# Supplements.net
KiCad netlist of a schematic drawn in Altium Designer
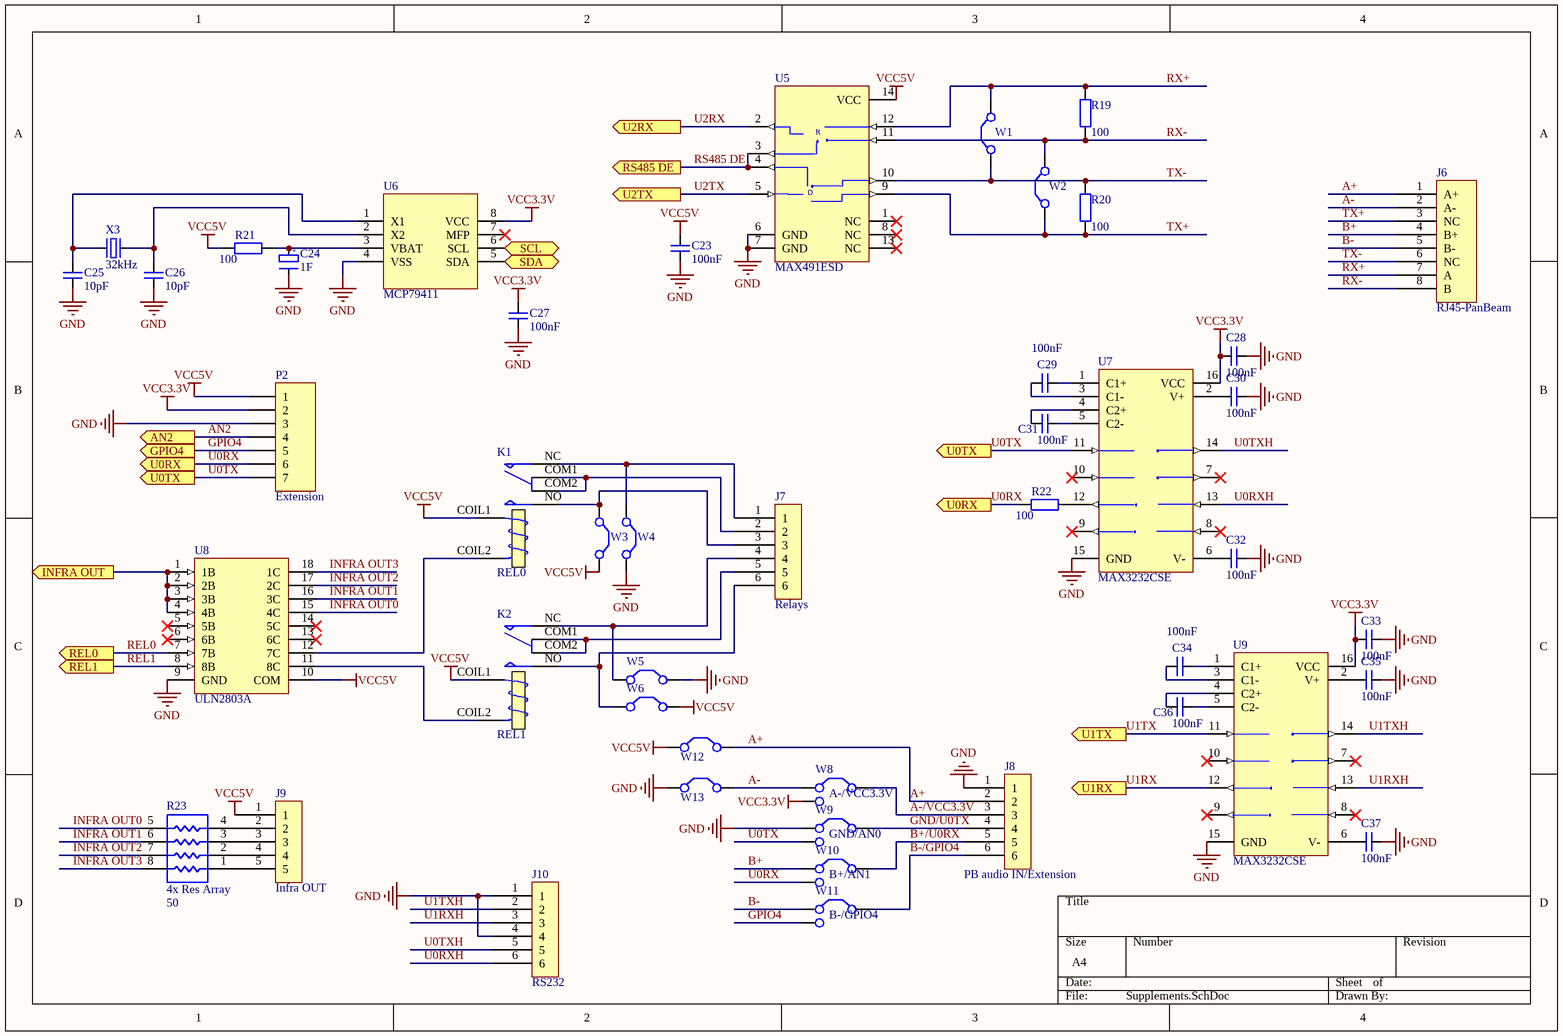
[diagram p0: Supplements.SchDoc]

(export (version "E")
  (design (tool "Eeschema 10.0.6"))
  (components
    (comp (ref "C23")
      (value "100nF")
      (footprint "0805 CAP")
      (description "Capacitor")
      (fields (field (name "Comment") "CAP"))
      (libsource (lib "EtherIOv2") (part "CAP"))
    )
    (comp (ref "C24")
      (value "1F")
      (footprint "Goldcap_1F")
      (description "Electrolit Capacitor")
      (fields (field (name "Comment") "ELKO"))
      (libsource (lib "EtherIOv2") (part "ELKO"))
    )
    (comp (ref "C25")
      (value "10pF")
      (footprint "0805 CAP")
      (description "Capacitor")
      (fields (field (name "Comment") "CAP"))
      (libsource (lib "EtherIOv2") (part "CAP"))
    )
    (comp (ref "C26")
      (value "10pF")
      (footprint "0805 CAP")
      (description "Capacitor")
      (fields (field (name "Comment") "CAP"))
      (libsource (lib "EtherIOv2") (part "CAP"))
    )
    (comp (ref "C27")
      (value "100nF")
      (footprint "0805 CAP")
      (description "Capacitor")
      (fields (field (name "Comment") "CAP"))
      (libsource (lib "EtherIOv2") (part "CAP"))
    )
    (comp (ref "C28")
      (value "100nF")
      (footprint "0805 CAP")
      (description "Capacitor")
      (fields (field (name "Comment") "CAP"))
      (libsource (lib "EtherIOv2") (part "CAP"))
    )
    (comp (ref "C29")
      (value "100nF")
      (footprint "0805 CAP")
      (description "Capacitor")
      (fields (field (name "Comment") "CAP"))
      (libsource (lib "EtherIOv2") (part "CAP"))
    )
    (comp (ref "C30")
      (value "100nF")
      (footprint "0805 CAP")
      (description "Capacitor")
      (fields (field (name "Comment") "CAP"))
      (libsource (lib "EtherIOv2") (part "CAP"))
    )
    (comp (ref "C31")
      (value "100nF")
      (footprint "0805 CAP")
      (description "Capacitor")
      (fields (field (name "Comment") "CAP"))
      (libsource (lib "EtherIOv2") (part "CAP"))
    )
    (comp (ref "C32")
      (value "100nF")
      (footprint "0805 CAP")
      (description "Capacitor")
      (fields (field (name "Comment") "CAP"))
      (libsource (lib "EtherIOv2") (part "CAP"))
    )
    (comp (ref "C33")
      (value "100nF")
      (footprint "0805 CAP")
      (description "Capacitor")
      (fields (field (name "Comment") "CAP"))
      (libsource (lib "EtherIOv2") (part "CAP"))
    )
    (comp (ref "C34")
      (value "100nF")
      (footprint "0805 CAP")
      (description "Capacitor")
      (fields (field (name "Comment") "CAP"))
      (libsource (lib "EtherIOv2") (part "CAP"))
    )
    (comp (ref "C35")
      (value "100nF")
      (footprint "0805 CAP")
      (description "Capacitor")
      (fields (field (name "Comment") "CAP"))
      (libsource (lib "EtherIOv2") (part "CAP"))
    )
    (comp (ref "C36")
      (value "100nF")
      (footprint "0805 CAP")
      (description "Capacitor")
      (fields (field (name "Comment") "CAP"))
      (libsource (lib "EtherIOv2") (part "CAP"))
    )
    (comp (ref "C37")
      (value "100nF")
      (footprint "0805 CAP")
      (description "Capacitor")
      (fields (field (name "Comment") "CAP"))
      (libsource (lib "EtherIOv2") (part "CAP"))
    )
    (comp (ref "J6")
      (value "RJ45-PanBeam")
      (footprint "JACK1.27-2H8B")
      (description "PanBeam - RS485 + 2xAudio")
      (libsource (lib "EtherIOv2") (part "RJ45-PanBeam"))
    )
    (comp (ref "J7")
      (value "Relays")
      (footprint "Euroblock 3.5pitch 6P")
      (libsource (lib "EtherIOv2") (part "Euroblock 6P connector"))
    )
    (comp (ref "J8")
      (value "PB audio IN/Extension")
      (footprint "Euroblock 3.5pitch 6P")
      (libsource (lib "EtherIOv2") (part "Euroblock 6P connector"))
    )
    (comp (ref "J9")
      (value "Infra OUT")
      (footprint "Euroblock 3.5pitch 5P")
      (libsource (lib "EtherIOv2") (part "Euroblock 5P connector"))
    )
    (comp (ref "J10")
      (value "RS232")
      (footprint "Euroblock 3.5pitch 6P")
      (libsource (lib "EtherIOv2") (part "Euroblock 6P connector"))
    )
    (comp (ref "K1")
      (value "REL0")
      (footprint "RSY-12")
      (description "SPDT Relay")
      (fields (field (name "PUBLISHER") "Altium Limited"))
      (libsource (lib "EtherIOv2") (part "Relay"))
    )
    (comp (ref "K2")
      (value "REL1")
      (footprint "RSY-12")
      (description "SPDT Relay")
      (fields (field (name "PUBLISHER") "Altium Limited"))
      (libsource (lib "EtherIOv2") (part "Relay"))
    )
    (comp (ref "P2")
      (value "Extension")
      (footprint "HDR1X7")
      (description "Header, 7-Pin")
      (fields (field (name "PUBLISHER") "Altium Limited"))
      (libsource (lib "Miscellaneous Connectors") (part "Header 7"))
    )
    (comp (ref "R19")
      (value "100")
      (footprint "0805 RES")
      (description "Resistor")
      (fields (field (name "Comment") "RES") (field (name "PUBLISHER") "Altium Limited"))
      (libsource (lib "") (part "RES_1"))
    )
    (comp (ref "R20")
      (value "100")
      (footprint "0805 RES")
      (description "Resistor")
      (fields (field (name "Comment") "RES") (field (name "PUBLISHER") "Altium Limited"))
      (libsource (lib "") (part "RES_1"))
    )
    (comp (ref "R21")
      (value "100")
      (footprint "0805 RES")
      (description "Resistor")
      (fields (field (name "Comment") "RES") (field (name "PUBLISHER") "Altium Limited"))
      (libsource (lib "EtherIOv2") (part "RES"))
    )
    (comp (ref "R22")
      (value "100")
      (footprint "0805 RES")
      (description "Resistor")
      (fields (field (name "Comment") "RES") (field (name "PUBLISHER") "Altium Limited"))
      (libsource (lib "EtherIOv2") (part "RES"))
    )
    (comp (ref "R23")
      (value "4x Res Array")
      (footprint "1206 4xRES ARRAY")
      (description "Isolated Resistor Network")
      (fields (field (name "ALTIUM_VALUE") "50") (field (name "PUBLISHER") "Altium Limited"))
      (libsource (lib "EtherIOv2") (part "4x Res Array"))
    )
    (comp (ref "U5")
      (value "MAX491ESD")
      (footprint "NSO14_N")
      (description "Low-Power, Slew-Rate-Limited RS-485/RS-422 Transceiver")
      (fields (field (name "PUBLISHER") "Altium Limited"))
      (libsource (lib "Maxim Communication Transceiver") (part "MAX491ESD"))
    )
    (comp (ref "U6")
      (value "MCP79411")
      (footprint "MSOP8")
      (description "MCP79411 I2C RTCC + MAC")
      (libsource (lib "EtherIOv2") (part "MCP79411"))
    )
    (comp (ref "U7")
      (value "MAX3232CSE")
      (footprint "NSO16_M")
      (description "3.0V TO 5.5V, Low-Power, up to 1Mbps, True RS-232 Transceiver Using Four 0.1µF External Capacitor")
      (fields (field (name "PUBLISHER") "Altium Limited"))
      (libsource (lib "Maxim Communication Transceiver") (part "MAX3232CSE"))
    )
    (comp (ref "U8")
      (value "ULN2803A")
      (footprint "SOIC127P1030X265-18N")
      (description "8xDarlington Driver")
      (libsource (lib "EtherIOv2") (part "ULN2803A"))
    )
    (comp (ref "U9")
      (value "MAX3232CSE")
      (footprint "NSO16_M")
      (description "3.0V TO 5.5V, Low-Power, up to 1Mbps, True RS-232 Transceiver Using Four 0.1µF External Capacitor")
      (fields (field (name "PUBLISHER") "Altium Limited"))
      (libsource (lib "Maxim Communication Transceiver") (part "MAX3232CSE"))
    )
    (comp (ref "W1")
      (value "Jumper")
      (footprint "Jumper")
      (description "Jumper Wire")
      (fields (field (name "PUBLISHER") "Altium Limited"))
      (libsource (lib "EtherIOv2") (part "Jumper"))
    )
    (comp (ref "W2")
      (value "Jumper")
      (footprint "Jumper")
      (description "Jumper Wire")
      (fields (field (name "PUBLISHER") "Altium Limited"))
      (libsource (lib "EtherIOv2") (part "Jumper"))
    )
    (comp (ref "W3")
      (value "Jumper")
      (footprint "Jumper")
      (description "Jumper Wire")
      (fields (field (name "PUBLISHER") "Altium Limited"))
      (libsource (lib "EtherIOv2") (part "Jumper"))
    )
    (comp (ref "W4")
      (value "Jumper")
      (footprint "Jumper")
      (description "Jumper Wire")
      (fields (field (name "PUBLISHER") "Altium Limited"))
      (libsource (lib "EtherIOv2") (part "Jumper"))
    )
    (comp (ref "W5")
      (value "Jumper")
      (footprint "Jumper")
      (description "Jumper Wire")
      (fields (field (name "PUBLISHER") "Altium Limited"))
      (libsource (lib "EtherIOv2") (part "Jumper"))
    )
    (comp (ref "W6")
      (value "Jumper")
      (footprint "Jumper")
      (description "Jumper Wire")
      (fields (field (name "PUBLISHER") "Altium Limited"))
      (libsource (lib "EtherIOv2") (part "Jumper"))
    )
    (comp (ref "W8")
      (value "A-/VCC3.3V")
      (footprint "0603 3WAY JUMPER")
      (description "Jumper Wire")
      (fields (field (name "PUBLISHER") "Altium Limited"))
      (libsource (lib "EtherIOv2") (part "Jumper_3way"))
    )
    (comp (ref "W9")
      (value "GND/AN0")
      (footprint "0603 3WAY JUMPER")
      (description "Jumper Wire")
      (fields (field (name "PUBLISHER") "Altium Limited"))
      (libsource (lib "EtherIOv2") (part "Jumper_3way"))
    )
    (comp (ref "W10")
      (value "B+/AN1")
      (footprint "0603 3WAY JUMPER")
      (description "Jumper Wire")
      (fields (field (name "PUBLISHER") "Altium Limited"))
      (libsource (lib "EtherIOv2") (part "Jumper_3way"))
    )
    (comp (ref "W11")
      (value "B-/GPIO4")
      (footprint "0603 3WAY JUMPER")
      (description "Jumper Wire")
      (fields (field (name "PUBLISHER") "Altium Limited"))
      (libsource (lib "EtherIOv2") (part "Jumper_3way"))
    )
    (comp (ref "W12")
      (value "Jumper")
      (footprint "Jumper")
      (description "Jumper Wire")
      (fields (field (name "PUBLISHER") "Altium Limited"))
      (libsource (lib "EtherIOv2") (part "Jumper"))
    )
    (comp (ref "W13")
      (value "Jumper")
      (footprint "Jumper")
      (description "Jumper Wire")
      (fields (field (name "PUBLISHER") "Altium Limited"))
      (libsource (lib "EtherIOv2") (part "Jumper"))
    )
    (comp (ref "X3")
      (value "32kHz")
      (footprint "CRYSTAL_mini")
      (description "Crystal")
      (fields (field (name "Comment") "CRYSTAL"))
      (libsource (lib "EtherIOv2") (part "CRYSTAL"))
    )
  )
  (nets
    (net (code "1") (name "/A+") (class "Default")
      (node (ref "J6") (pin "1") (pinfunction "A+_1") (pintype "passive"))
      (node (ref "J8") (pin "2") (pinfunction "2_2") (pintype "passive"))
      (node (ref "W12") (pin "2") (pinfunction "C2_2") (pintype "passive"))
    )
    (net (code "2") (name "/A-") (class "Default")
      (node (ref "J6") (pin "2") (pinfunction "A-_2") (pintype "passive"))
      (node (ref "W13") (pin "2") (pinfunction "C2_2") (pintype "passive"))
      (node (ref "W8") (pin "1") (pinfunction "C1_1") (pintype "passive"))
    )
    (net (code "3") (name "/A-{slash}VCC3.3V") (class "Default")
      (node (ref "J8") (pin "3") (pinfunction "3_3") (pintype "passive"))
      (node (ref "W8") (pin "2") (pinfunction "C2_2") (pintype "passive"))
    )
    (net (code "4") (name "/AN2") (class "Default")
      (node (ref "P2") (pin "4") (pinfunction "4_4") (pintype "passive"))
    )
    (net (code "5") (name "/B+") (class "Default")
      (node (ref "J6") (pin "4") (pinfunction "B+_4") (pintype "passive"))
      (node (ref "W10") (pin "1") (pinfunction "C1_1") (pintype "passive"))
    )
    (net (code "6") (name "/B+{slash}U0RX") (class "Default")
      (node (ref "J8") (pin "5") (pinfunction "5_5") (pintype "passive"))
      (node (ref "W10") (pin "2") (pinfunction "C2_2") (pintype "passive"))
    )
    (net (code "7") (name "/B-") (class "Default")
      (node (ref "J6") (pin "5") (pinfunction "B-_5") (pintype "passive"))
      (node (ref "W11") (pin "1") (pinfunction "C1_1") (pintype "passive"))
    )
    (net (code "8") (name "/B-{slash}GPIO4") (class "Default")
      (node (ref "J8") (pin "6") (pinfunction "6_6") (pintype "passive"))
      (node (ref "W11") (pin "2") (pinfunction "C2_2") (pintype "passive"))
    )
    (net (code "9") (name "/GND{slash}U0TX") (class "Default")
      (node (ref "J8") (pin "4") (pinfunction "4_4") (pintype "passive"))
      (node (ref "W9") (pin "2") (pinfunction "C2_2") (pintype "passive"))
    )
    (net (code "10") (name "/GPIO4") (class "Default")
      (node (ref "P2") (pin "5") (pinfunction "5_5") (pintype "passive"))
      (node (ref "W11") (pin "3") (pinfunction "C1_3") (pintype "passive"))
    )
    (net (code "11") (name "/INFRA OUT") (class "Default")
      (node (ref "U8") (pin "1") (pinfunction "1B_1") (pintype "input"))
      (node (ref "U8") (pin "2") (pinfunction "2B_2") (pintype "input"))
      (node (ref "U8") (pin "3") (pinfunction "3B_3") (pintype "input"))
      (node (ref "U8") (pin "4") (pinfunction "4B_4") (pintype "input"))
    )
    (net (code "12") (name "/INFRA OUT0") (class "Default")
      (node (ref "R23") (pin "5") (pinfunction "5_5") (pintype "passive"))
      (node (ref "U8") (pin "15") (pinfunction "4C_15") (pintype "open_collector"))
    )
    (net (code "13") (name "/INFRA OUT1") (class "Default")
      (node (ref "R23") (pin "6") (pinfunction "6_6") (pintype "passive"))
      (node (ref "U8") (pin "16") (pinfunction "3C_16") (pintype "open_collector"))
    )
    (net (code "14") (name "/INFRA OUT2") (class "Default")
      (node (ref "R23") (pin "7") (pinfunction "7_7") (pintype "passive"))
      (node (ref "U8") (pin "17") (pinfunction "2C_17") (pintype "open_collector"))
    )
    (net (code "15") (name "/INFRA OUT3") (class "Default")
      (node (ref "R23") (pin "8") (pinfunction "8_8") (pintype "passive"))
      (node (ref "U8") (pin "18") (pinfunction "1C_18") (pintype "open_collector"))
    )
    (net (code "16") (name "/REL0") (class "Default")
      (node (ref "U8") (pin "7") (pinfunction "7B_7") (pintype "input"))
    )
    (net (code "17") (name "/REL1") (class "Default")
      (node (ref "U8") (pin "8") (pinfunction "8B_8") (pintype "input"))
    )
    (net (code "18") (name "/RS485 DE") (class "Default")
      (node (ref "U5") (pin "3") (pinfunction "~{RE}_3") (pintype "output"))
      (node (ref "U5") (pin "4") (pinfunction "DE_4") (pintype "output"))
    )
    (net (code "19") (name "/RX+") (class "Default")
      (node (ref "J6") (pin "7") (pinfunction "A_7") (pintype "passive"))
      (node (ref "R19") (pin "2") (pinfunction "2_2") (pintype "passive"))
      (node (ref "U5") (pin "12") (pinfunction "A_12") (pintype "input"))
      (node (ref "W1") (pin "2") (pinfunction "C2_2") (pintype "passive"))
    )
    (net (code "20") (name "/RX-") (class "Default")
      (node (ref "J6") (pin "8") (pinfunction "B_8") (pintype "passive"))
      (node (ref "R19") (pin "1") (pinfunction "1_1") (pintype "passive"))
      (node (ref "U5") (pin "11") (pinfunction "B_11") (pintype "input"))
      (node (ref "W2") (pin "2") (pinfunction "C2_2") (pintype "passive"))
    )
    (net (code "21") (name "/SCL") (class "Default")
      (node (ref "U6") (pin "6") (pinfunction "SCL_6") (pintype "passive"))
    )
    (net (code "22") (name "/SDA") (class "Default")
      (node (ref "U6") (pin "5") (pinfunction "SDA_5") (pintype "passive"))
    )
    (net (code "23") (name "/TX+") (class "Default")
      (node (ref "J6") (pin "3") (pinfunction "NC_3") (pintype "passive"))
      (node (ref "R20") (pin "1") (pinfunction "1_1") (pintype "passive"))
      (node (ref "U5") (pin "9") (pinfunction "Y_9") (pintype "output"))
      (node (ref "W2") (pin "1") (pinfunction "C1_1") (pintype "passive"))
    )
    (net (code "24") (name "/TX-") (class "Default")
      (node (ref "J6") (pin "6") (pinfunction "NC_6") (pintype "passive"))
      (node (ref "R20") (pin "2") (pinfunction "2_2") (pintype "passive"))
      (node (ref "U5") (pin "10") (pinfunction "Z_10") (pintype "output"))
      (node (ref "W1") (pin "1") (pinfunction "C1_1") (pintype "passive"))
    )
    (net (code "25") (name "/U0RX") (class "Default")
      (node (ref "P2") (pin "6") (pinfunction "6_6") (pintype "passive"))
      (node (ref "R22") (pin "1") (pinfunction "1_1") (pintype "passive"))
      (node (ref "W10") (pin "3") (pinfunction "C1_3") (pintype "passive"))
    )
    (net (code "26") (name "/U0RXH") (class "Default")
      (node (ref "J10") (pin "6") (pinfunction "6_6") (pintype "passive"))
      (node (ref "U7") (pin "13") (pinfunction "R1IN_13") (pintype "input"))
    )
    (net (code "27") (name "/U0TX") (class "Default")
      (node (ref "P2") (pin "7") (pinfunction "7_7") (pintype "passive"))
      (node (ref "U7") (pin "11") (pinfunction "T1IN_11") (pintype "input"))
      (node (ref "W9") (pin "3") (pinfunction "C1_3") (pintype "passive"))
    )
    (net (code "28") (name "/U0TXH") (class "Default")
      (node (ref "J10") (pin "5") (pinfunction "5_5") (pintype "passive"))
      (node (ref "U7") (pin "14") (pinfunction "T1OUT_14") (pintype "output"))
    )
    (net (code "29") (name "/U1RX") (class "Default")
      (node (ref "U9") (pin "12") (pinfunction "R1OUT_12") (pintype "output"))
    )
    (net (code "30") (name "/U1RXH") (class "Default")
      (node (ref "J10") (pin "3") (pinfunction "3_3") (pintype "passive"))
      (node (ref "U9") (pin "13") (pinfunction "R1IN_13") (pintype "input"))
    )
    (net (code "31") (name "/U1TX") (class "Default")
      (node (ref "U9") (pin "11") (pinfunction "T1IN_11") (pintype "input"))
    )
    (net (code "32") (name "/U1TXH") (class "Default")
      (node (ref "J10") (pin "2") (pinfunction "2_2") (pintype "passive"))
      (node (ref "U9") (pin "14") (pinfunction "T1OUT_14") (pintype "output"))
    )
    (net (code "33") (name "/U2RX") (class "Default")
      (node (ref "U5") (pin "2") (pinfunction "RO_2") (pintype "output"))
    )
    (net (code "34") (name "/U2TX") (class "Default")
      (node (ref "U5") (pin "5") (pinfunction "DI_5") (pintype "input"))
    )
    (net (code "35") (name "GND") (class "Default")
      (node (ref "C23") (pin "2") (pinfunction "B_2") (pintype "passive"))
      (node (ref "C24") (pin "1") (pinfunction "B_1") (pintype "passive"))
      (node (ref "C25") (pin "1") (pinfunction "A_1") (pintype "passive"))
      (node (ref "C26") (pin "1") (pinfunction "A_1") (pintype "passive"))
      (node (ref "C27") (pin "2") (pinfunction "B_2") (pintype "passive"))
      (node (ref "C28") (pin "2") (pinfunction "B_2") (pintype "passive"))
      (node (ref "C30") (pin "2") (pinfunction "B_2") (pintype "passive"))
      (node (ref "C32") (pin "2") (pinfunction "B_2") (pintype "passive"))
      (node (ref "C33") (pin "2") (pinfunction "B_2") (pintype "passive"))
      (node (ref "C35") (pin "2") (pinfunction "B_2") (pintype "passive"))
      (node (ref "C37") (pin "2") (pinfunction "B_2") (pintype "passive"))
      (node (ref "J10") (pin "1") (pinfunction "1_1") (pintype "passive"))
      (node (ref "J10") (pin "4") (pinfunction "4_4") (pintype "passive"))
      (node (ref "J8") (pin "1") (pinfunction "1_1") (pintype "passive"))
      (node (ref "P2") (pin "3") (pinfunction "3_3") (pintype "passive"))
      (node (ref "U5") (pin "6") (pinfunction "GND_6") (pintype "power_in"))
      (node (ref "U5") (pin "7") (pinfunction "GND_7") (pintype "power_in"))
      (node (ref "U6") (pin "4") (pinfunction "VSS_4") (pintype "passive"))
      (node (ref "U7") (pin "15") (pinfunction "GND_15") (pintype "power_in"))
      (node (ref "U8") (pin "9") (pinfunction "GND_9") (pintype "power_in"))
      (node (ref "U9") (pin "15") (pinfunction "GND_15") (pintype "power_in"))
      (node (ref "W13") (pin "1") (pinfunction "C1_1") (pintype "passive"))
      (node (ref "W4") (pin "2") (pinfunction "C2_2") (pintype "passive"))
      (node (ref "W5") (pin "2") (pinfunction "C2_2") (pintype "passive"))
      (node (ref "W9") (pin "1") (pinfunction "C1_1") (pintype "passive"))
    )
    (net (code "36") (name "Net-(C24-A)") (class "Default")
      (node (ref "C24") (pin "2") (pinfunction "A_2") (pintype "passive"))
      (node (ref "R21") (pin "2") (pinfunction "2_2") (pintype "passive"))
      (node (ref "U6") (pin "3") (pinfunction "VBAT_3") (pintype "passive"))
    )
    (net (code "37") (name "Net-(C25-B)") (class "Default")
      (node (ref "C25") (pin "2") (pinfunction "B_2") (pintype "passive"))
      (node (ref "U6") (pin "1") (pinfunction "X1_1") (pintype "passive"))
      (node (ref "X3") (pin "1") (pinfunction "A_1") (pintype "passive"))
    )
    (net (code "38") (name "Net-(C26-B)") (class "Default")
      (node (ref "C26") (pin "2") (pinfunction "B_2") (pintype "passive"))
      (node (ref "U6") (pin "2") (pinfunction "X2_2") (pintype "passive"))
      (node (ref "X3") (pin "2") (pinfunction "B_2") (pintype "passive"))
    )
    (net (code "39") (name "Net-(C29-A)") (class "Default")
      (node (ref "C29") (pin "1") (pinfunction "A_1") (pintype "passive"))
      (node (ref "U7") (pin "3") (pinfunction "C1-_3") (pintype "passive"))
    )
    (net (code "40") (name "Net-(C29-B)") (class "Default")
      (node (ref "C29") (pin "2") (pinfunction "B_2") (pintype "passive"))
      (node (ref "U7") (pin "1") (pinfunction "C1+_1") (pintype "passive"))
    )
    (net (code "41") (name "Net-(C30-A)") (class "Default")
      (node (ref "C30") (pin "1") (pinfunction "A_1") (pintype "passive"))
      (node (ref "U7") (pin "2") (pinfunction "V+_2") (pintype "power_in"))
    )
    (net (code "42") (name "Net-(C31-A)") (class "Default")
      (node (ref "C31") (pin "1") (pinfunction "A_1") (pintype "passive"))
      (node (ref "U7") (pin "4") (pinfunction "C2+_4") (pintype "passive"))
    )
    (net (code "43") (name "Net-(C31-B)") (class "Default")
      (node (ref "C31") (pin "2") (pinfunction "B_2") (pintype "passive"))
      (node (ref "U7") (pin "5") (pinfunction "C2-_5") (pintype "passive"))
    )
    (net (code "44") (name "Net-(C32-A)") (class "Default")
      (node (ref "C32") (pin "1") (pinfunction "A_1") (pintype "passive"))
      (node (ref "U7") (pin "6") (pinfunction "V-_6") (pintype "power_in"))
    )
    (net (code "45") (name "Net-(C34-A)") (class "Default")
      (node (ref "C34") (pin "1") (pinfunction "A_1") (pintype "passive"))
      (node (ref "U9") (pin "3") (pinfunction "C1-_3") (pintype "passive"))
    )
    (net (code "46") (name "Net-(C34-B)") (class "Default")
      (node (ref "C34") (pin "2") (pinfunction "B_2") (pintype "passive"))
      (node (ref "U9") (pin "1") (pinfunction "C1+_1") (pintype "passive"))
    )
    (net (code "47") (name "Net-(C35-A)") (class "Default")
      (node (ref "C35") (pin "1") (pinfunction "A_1") (pintype "passive"))
      (node (ref "U9") (pin "2") (pinfunction "V+_2") (pintype "power_in"))
    )
    (net (code "48") (name "Net-(C36-A)") (class "Default")
      (node (ref "C36") (pin "1") (pinfunction "A_1") (pintype "passive"))
      (node (ref "U9") (pin "4") (pinfunction "C2+_4") (pintype "passive"))
    )
    (net (code "49") (name "Net-(C36-B)") (class "Default")
      (node (ref "C36") (pin "2") (pinfunction "B_2") (pintype "passive"))
      (node (ref "U9") (pin "5") (pinfunction "C2-_5") (pintype "passive"))
    )
    (net (code "50") (name "Net-(C37-A)") (class "Default")
      (node (ref "C37") (pin "1") (pinfunction "A_1") (pintype "passive"))
      (node (ref "U9") (pin "6") (pinfunction "V-_6") (pintype "power_in"))
    )
    (net (code "51") (name "Net-(J7-Pad2)") (class "Default")
      (node (ref "J7") (pin "2") (pinfunction "2_2") (pintype "passive"))
      (node (ref "K1") (pin "COM1") (pinfunction "COM_COM1") (pintype "passive"))
      (node (ref "K1") (pin "COM2") (pinfunction "COM_COM2") (pintype "passive"))
    )
    (net (code "52") (name "Net-(J7-Pad5)") (class "Default")
      (node (ref "J7") (pin "5") (pinfunction "5_5") (pintype "passive"))
      (node (ref "K2") (pin "COM1") (pinfunction "COM_COM1") (pintype "passive"))
      (node (ref "K2") (pin "COM2") (pinfunction "COM_COM2") (pintype "passive"))
    )
    (net (code "53") (name "Net-(J9-Pad2)") (class "Default")
      (node (ref "J9") (pin "2") (pinfunction "2_2") (pintype "passive"))
      (node (ref "R23") (pin "4") (pinfunction "4_4") (pintype "passive"))
    )
    (net (code "54") (name "Net-(J9-Pad3)") (class "Default")
      (node (ref "J9") (pin "3") (pinfunction "3_3") (pintype "passive"))
      (node (ref "R23") (pin "3") (pinfunction "3_3") (pintype "passive"))
    )
    (net (code "55") (name "Net-(J9-Pad4)") (class "Default")
      (node (ref "J9") (pin "4") (pinfunction "4_4") (pintype "passive"))
      (node (ref "R23") (pin "2") (pinfunction "2_2") (pintype "passive"))
    )
    (net (code "56") (name "Net-(J9-Pad5)") (class "Default")
      (node (ref "J9") (pin "5") (pinfunction "5_5") (pintype "passive"))
      (node (ref "R23") (pin "1") (pinfunction "1_1") (pintype "passive"))
    )
    (net (code "57") (name "Net-(U7-R1OUT)") (class "Default")
      (node (ref "R22") (pin "2") (pinfunction "2_2") (pintype "passive"))
      (node (ref "U7") (pin "12") (pinfunction "R1OUT_12") (pintype "output"))
    )
    (net (code "58") (name "Net-(U8-7C)") (class "Default")
      (node (ref "K1") (pin "COIL2") (pinfunction "COIL2_COIL2") (pintype "passive"))
      (node (ref "U8") (pin "12") (pinfunction "7C_12") (pintype "open_collector"))
    )
    (net (code "59") (name "Net-(U8-8C)") (class "Default")
      (node (ref "K2") (pin "COIL2") (pinfunction "COIL2_COIL2") (pintype "passive"))
      (node (ref "U8") (pin "11") (pinfunction "8C_11") (pintype "open_collector"))
    )
    (net (code "60") (name "Net-(W3-C1)") (class "Default")
      (node (ref "J7") (pin "3") (pinfunction "3_3") (pintype "passive"))
      (node (ref "K1") (pin "NO") (pinfunction "NO_NO") (pintype "passive"))
      (node (ref "W3") (pin "1") (pinfunction "C1_1") (pintype "passive"))
    )
    (net (code "61") (name "Net-(W4-C1)") (class "Default")
      (node (ref "J7") (pin "1") (pinfunction "1_1") (pintype "passive"))
      (node (ref "K1") (pin "NC") (pinfunction "NC_NC") (pintype "passive"))
      (node (ref "W4") (pin "1") (pinfunction "C1_1") (pintype "passive"))
    )
    (net (code "62") (name "Net-(W5-C1)") (class "Default")
      (node (ref "J7") (pin "4") (pinfunction "4_4") (pintype "passive"))
      (node (ref "K2") (pin "NC") (pinfunction "NC_NC") (pintype "passive"))
      (node (ref "W5") (pin "1") (pinfunction "C1_1") (pintype "passive"))
    )
    (net (code "63") (name "Net-(W6-C1)") (class "Default")
      (node (ref "J7") (pin "6") (pinfunction "6_6") (pintype "passive"))
      (node (ref "K2") (pin "NO") (pinfunction "NO_NO") (pintype "passive"))
      (node (ref "W6") (pin "1") (pinfunction "C1_1") (pintype "passive"))
    )
    (net (code "64") (name "VCC3.3V") (class "Default")
      (node (ref "C27") (pin "1") (pinfunction "A_1") (pintype "passive"))
      (node (ref "C28") (pin "1") (pinfunction "A_1") (pintype "passive"))
      (node (ref "C33") (pin "1") (pinfunction "A_1") (pintype "passive"))
      (node (ref "P2") (pin "2") (pinfunction "2_2") (pintype "passive"))
      (node (ref "U6") (pin "8") (pinfunction "VCC_8") (pintype "passive"))
      (node (ref "U7") (pin "16") (pinfunction "VCC_16") (pintype "power_in"))
      (node (ref "U9") (pin "16") (pinfunction "VCC_16") (pintype "power_in"))
      (node (ref "W8") (pin "3") (pinfunction "C1_3") (pintype "passive"))
    )
    (net (code "65") (name "VCC5V") (class "Default")
      (node (ref "C23") (pin "1") (pinfunction "A_1") (pintype "passive"))
      (node (ref "J9") (pin "1") (pinfunction "1_1") (pintype "passive"))
      (node (ref "K1") (pin "COIL1") (pinfunction "COIL1_COIL1") (pintype "passive"))
      (node (ref "K2") (pin "COIL1") (pinfunction "COIL1_COIL1") (pintype "passive"))
      (node (ref "P2") (pin "1") (pinfunction "1_1") (pintype "passive"))
      (node (ref "R21") (pin "1") (pinfunction "1_1") (pintype "passive"))
      (node (ref "U5") (pin "14") (pinfunction "VCC_14") (pintype "power_in"))
      (node (ref "U8") (pin "10") (pinfunction "COM_10") (pintype "power_in"))
      (node (ref "W12") (pin "1") (pinfunction "C1_1") (pintype "passive"))
      (node (ref "W3") (pin "2") (pinfunction "C2_2") (pintype "passive"))
      (node (ref "W6") (pin "2") (pinfunction "C2_2") (pintype "passive"))
    )
    (net (code "66") (name "unconnected-(U5-NC-Pad1)") (class "Default")
      (node (ref "U5") (pin "1") (pinfunction "NC_1") (pintype "passive+no_connect"))
    )
    (net (code "67") (name "unconnected-(U5-NC-Pad8)") (class "Default")
      (node (ref "U5") (pin "8") (pinfunction "NC_8") (pintype "passive+no_connect"))
    )
    (net (code "68") (name "unconnected-(U5-NC-Pad13)") (class "Default")
      (node (ref "U5") (pin "13") (pinfunction "NC_13") (pintype "passive+no_connect"))
    )
    (net (code "69") (name "unconnected-(U6-MFP-Pad7)") (class "Default")
      (node (ref "U6") (pin "7") (pinfunction "MFP_7") (pintype "passive+no_connect"))
    )
    (net (code "70") (name "unconnected-(U7-R2IN-Pad8)") (class "Default")
      (node (ref "U7") (pin "8") (pinfunction "R2IN_8") (pintype "input+no_connect"))
    )
    (net (code "71") (name "unconnected-(U7-R2OUT-Pad9)") (class "Default")
      (node (ref "U7") (pin "9") (pinfunction "R2OUT_9") (pintype "output+no_connect"))
    )
    (net (code "72") (name "unconnected-(U7-T2IN-Pad10)") (class "Default")
      (node (ref "U7") (pin "10") (pinfunction "T2IN_10") (pintype "input+no_connect"))
    )
    (net (code "73") (name "unconnected-(U7-T2OUT-Pad7)") (class "Default")
      (node (ref "U7") (pin "7") (pinfunction "T2OUT_7") (pintype "output+no_connect"))
    )
    (net (code "74") (name "unconnected-(U8-5B-Pad5)") (class "Default")
      (node (ref "U8") (pin "5") (pinfunction "5B_5") (pintype "input+no_connect"))
    )
    (net (code "75") (name "unconnected-(U8-5C-Pad14)") (class "Default")
      (node (ref "U8") (pin "14") (pinfunction "5C_14") (pintype "open_collector+no_connect"))
    )
    (net (code "76") (name "unconnected-(U8-6B-Pad6)") (class "Default")
      (node (ref "U8") (pin "6") (pinfunction "6B_6") (pintype "input+no_connect"))
    )
    (net (code "77") (name "unconnected-(U8-6C-Pad13)") (class "Default")
      (node (ref "U8") (pin "13") (pinfunction "6C_13") (pintype "open_collector+no_connect"))
    )
    (net (code "78") (name "unconnected-(U9-R2IN-Pad8)") (class "Default")
      (node (ref "U9") (pin "8") (pinfunction "R2IN_8") (pintype "input+no_connect"))
    )
    (net (code "79") (name "unconnected-(U9-R2OUT-Pad9)") (class "Default")
      (node (ref "U9") (pin "9") (pinfunction "R2OUT_9") (pintype "output+no_connect"))
    )
    (net (code "80") (name "unconnected-(U9-T2IN-Pad10)") (class "Default")
      (node (ref "U9") (pin "10") (pinfunction "T2IN_10") (pintype "input+no_connect"))
    )
    (net (code "81") (name "unconnected-(U9-T2OUT-Pad7)") (class "Default")
      (node (ref "U9") (pin "7") (pinfunction "T2OUT_7") (pintype "output+no_connect"))
    )
  )
)
